# SenseBox-Eye_v1_5.net
KiCad netlist of a schematic drawn in EAGLE
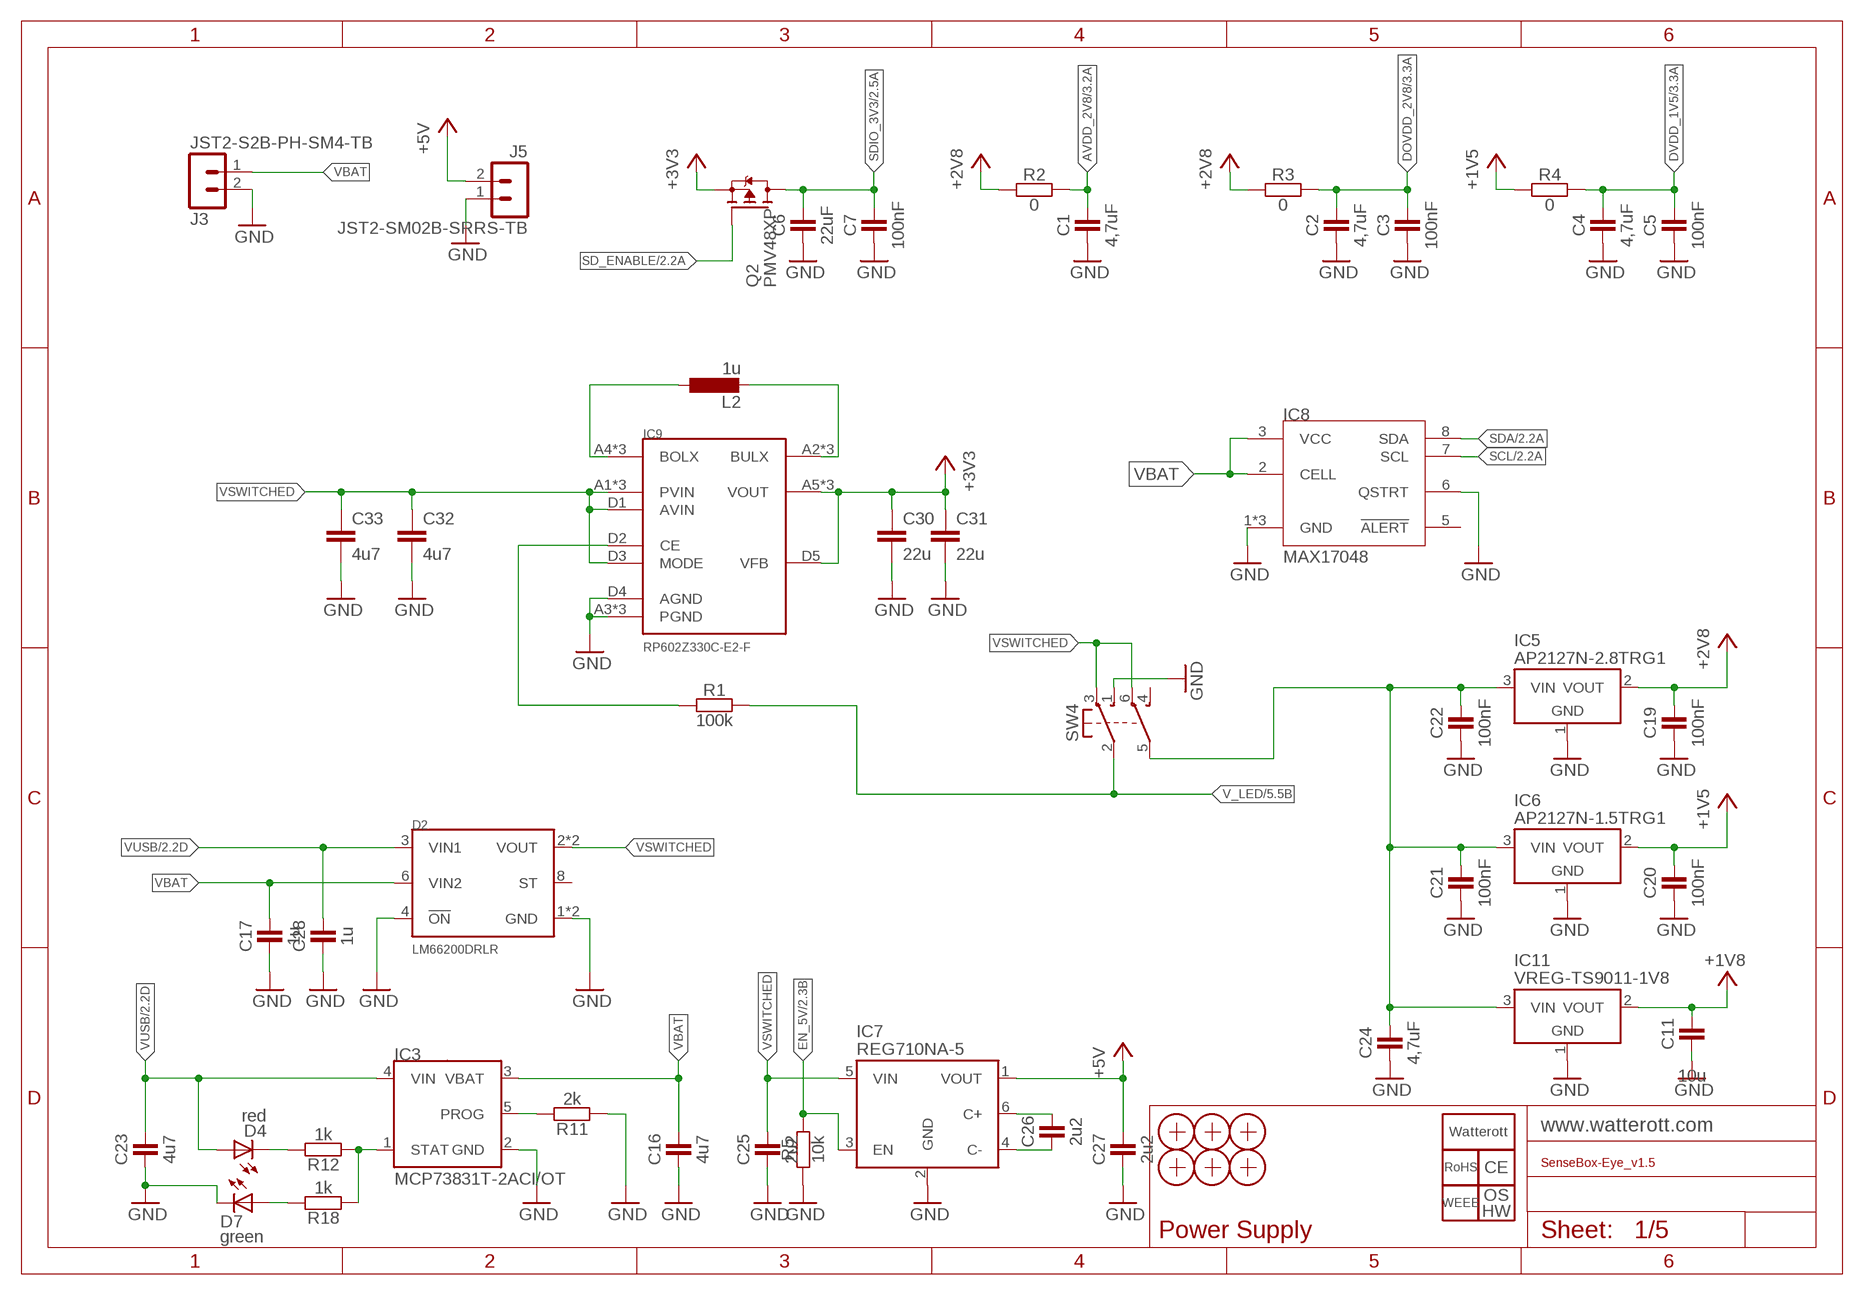
[diagram p0: schematic, sheet 1]
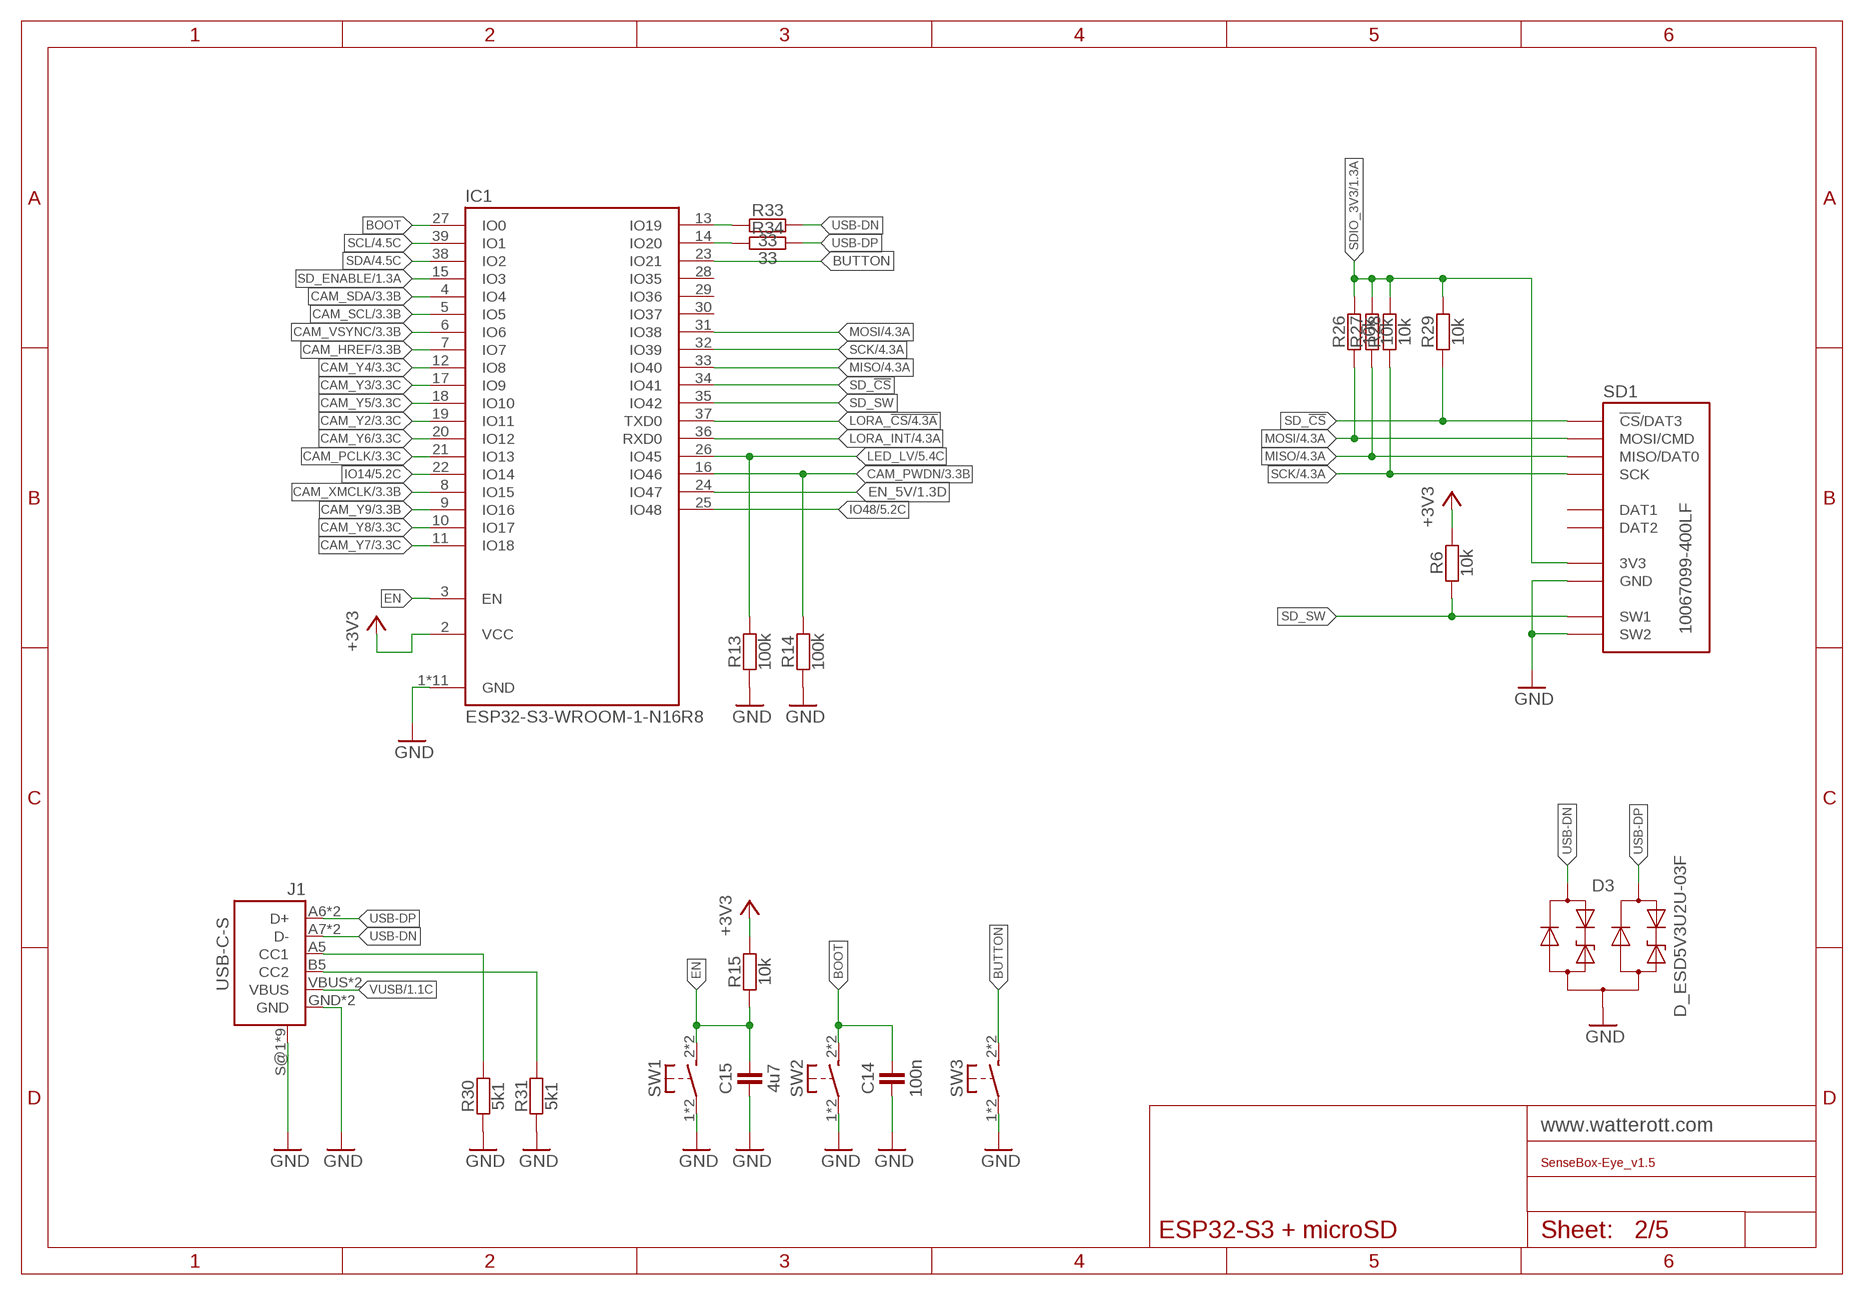
[diagram p1: schematic, sheet 2]
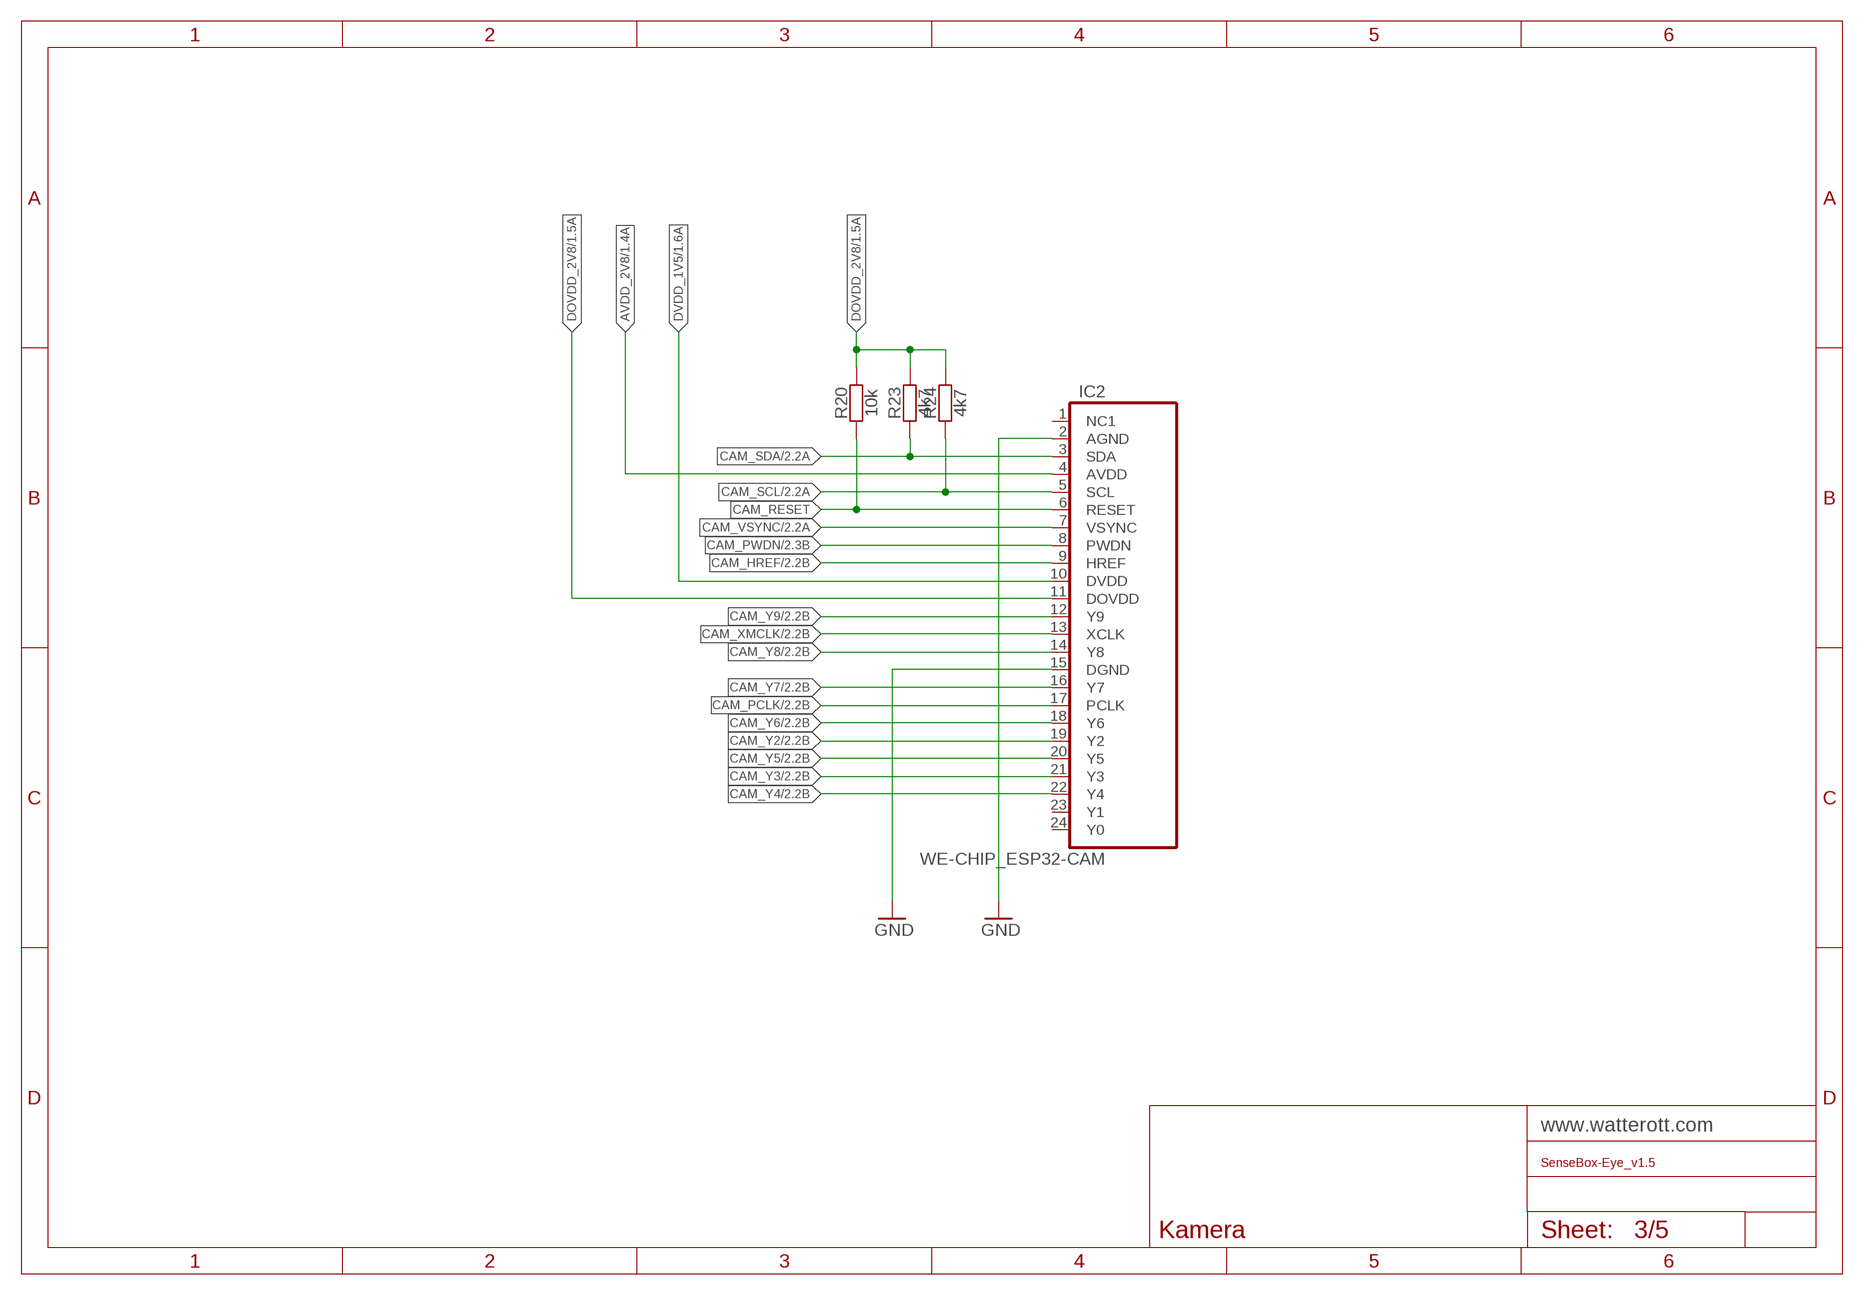
[diagram p2: schematic, sheet 3]
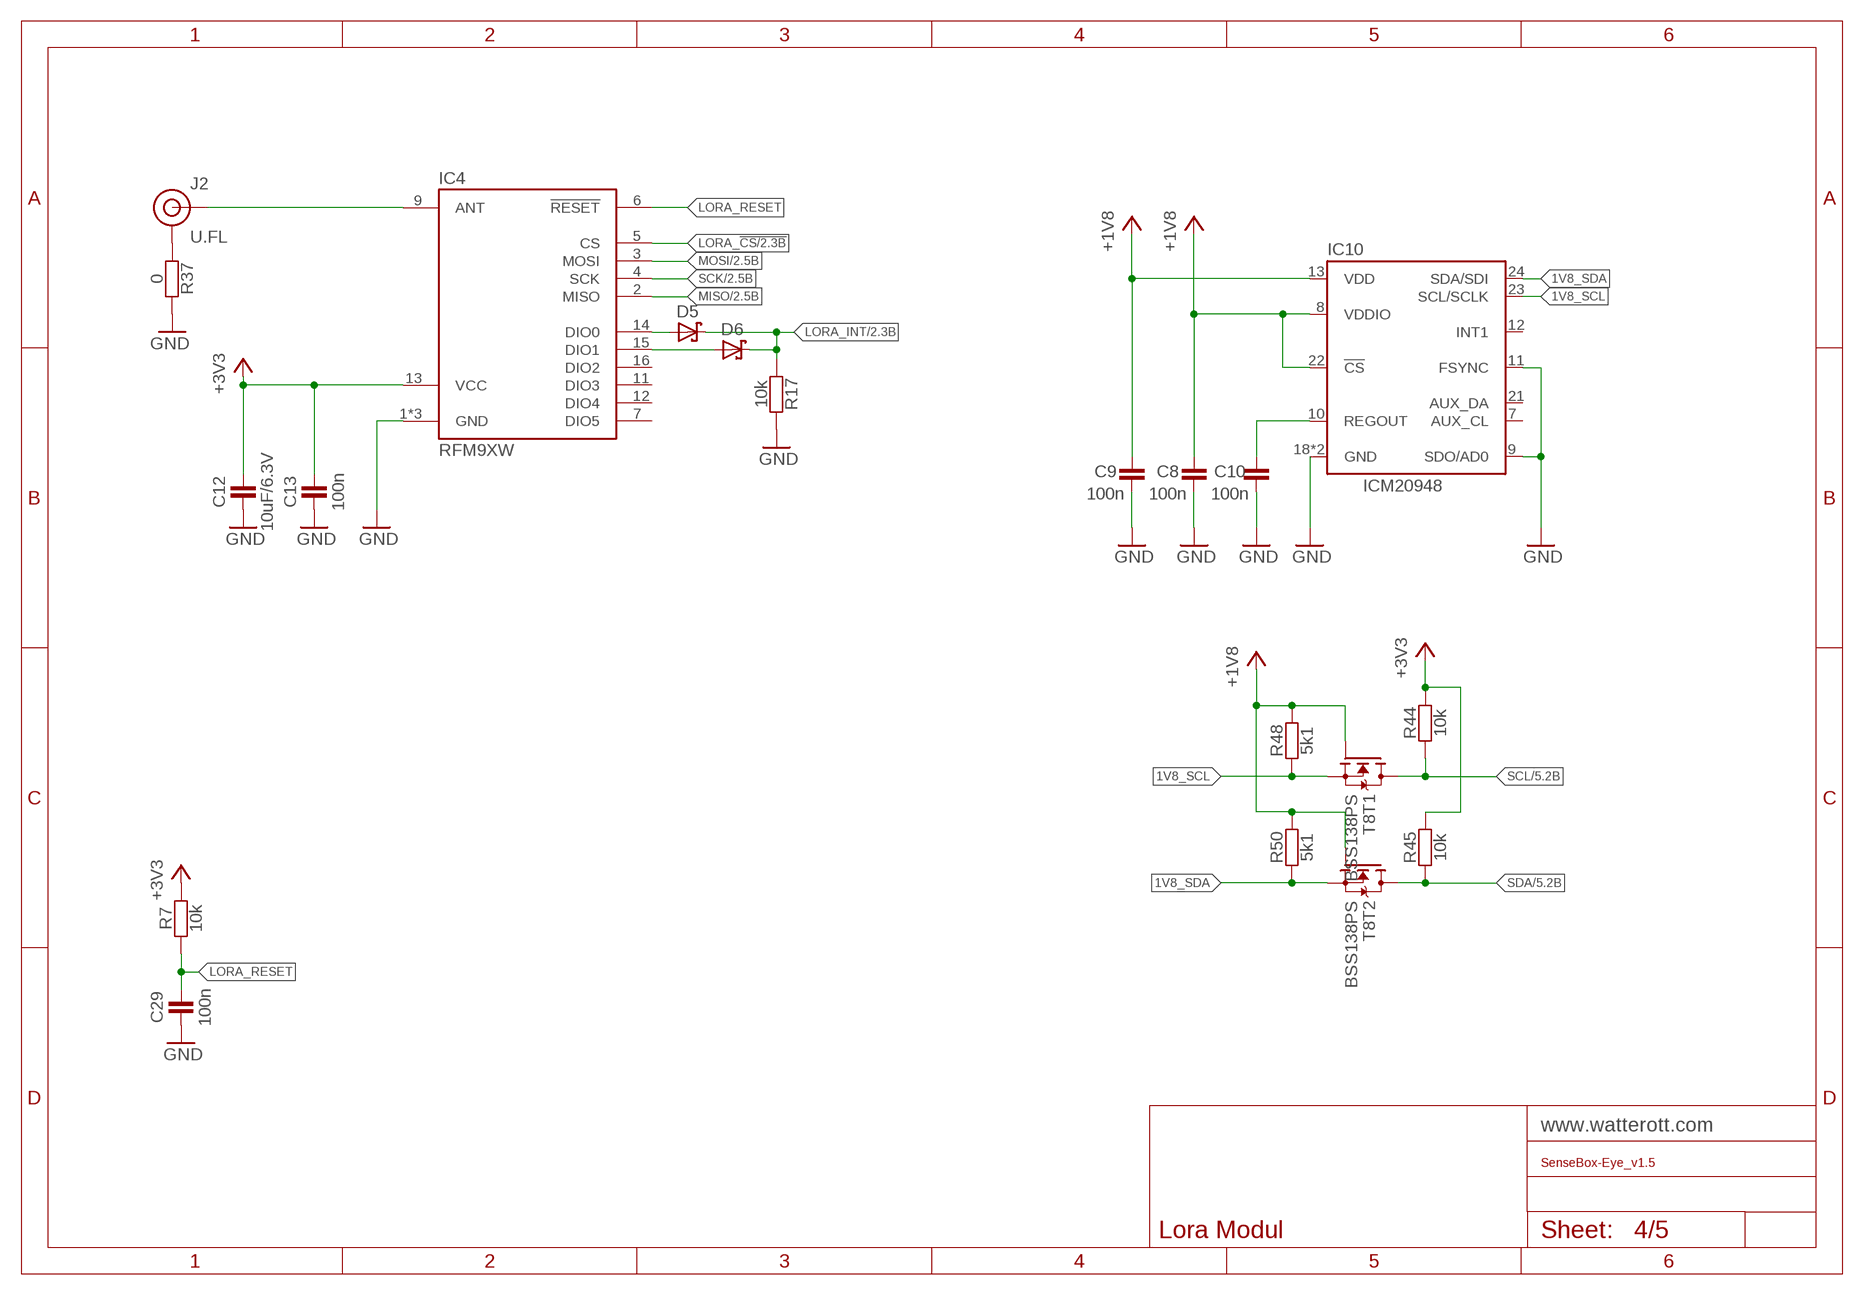
[diagram p3: schematic, sheet 4]
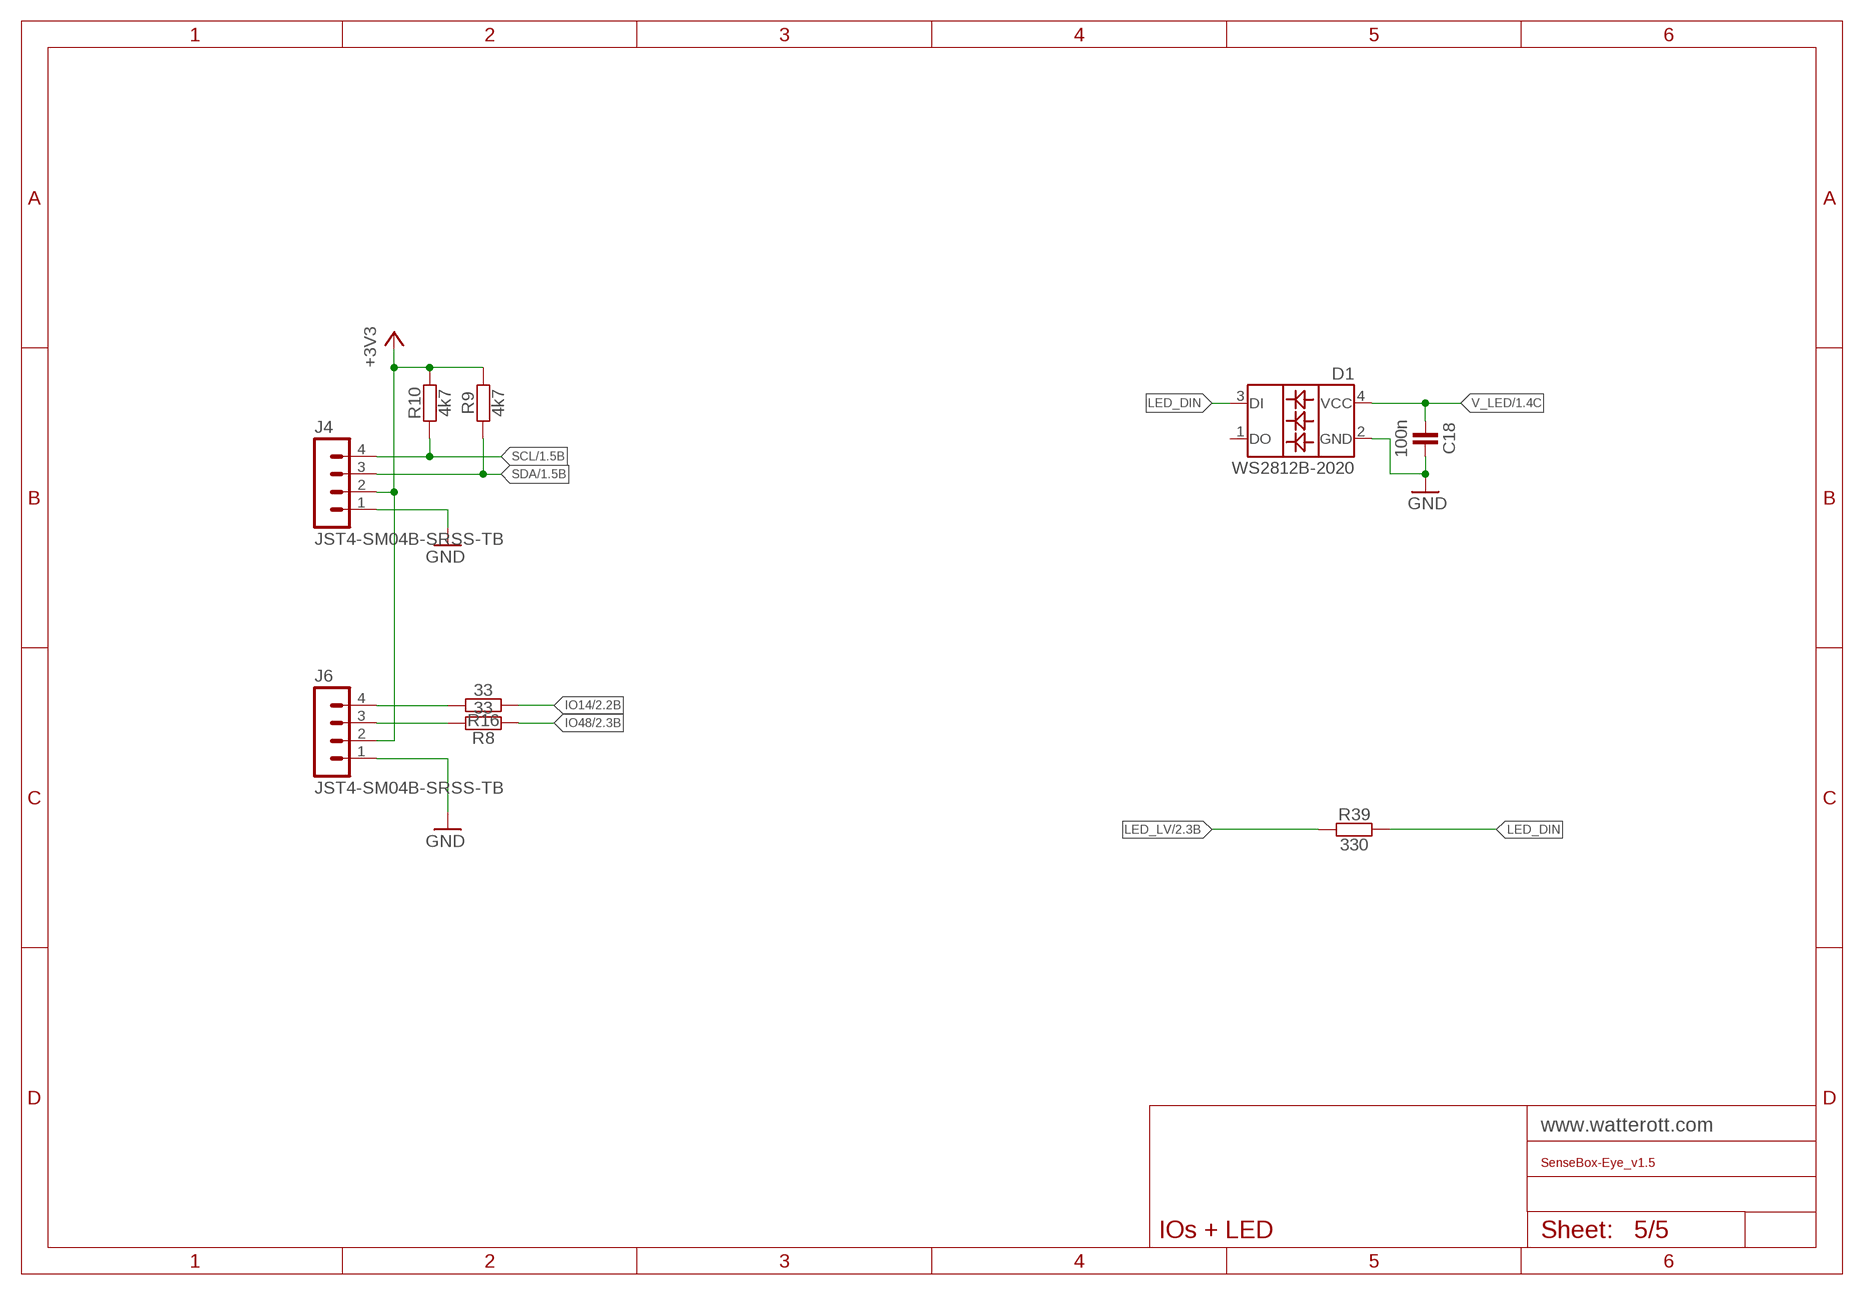
[diagram p4: schematic, sheet 5]

(export (version "E")
  (design (tool "Eeschema 10.0.6"))
  (components
    (comp (ref "C14")
      (value "100n")
      (footprint "eagle-import:C0402")
      (libsource (lib "eagle-import") (part "CAPACITOR-0402"))
    )
    (comp (ref "C15")
      (value "4u7")
      (footprint "eagle-import:C0402")
      (libsource (lib "eagle-import") (part "CAPACITOR-0402"))
    )
    (comp (ref "D3")
      (value "D_ESD5V3U2U-03F")
      (footprint "eagle-import:SOT723")
      (libsource (lib "eagle-import") (part "D_ESD5V3U2U-03F"))
    )
    (comp (ref "IC1")
      (value "ESP32-S3-WROOM-1-N16R8")
      (footprint "eagle-import:ESP32-S3-WROOM-1")
      (libsource (lib "eagle-import") (part "ESP32_S3-WROOM-1"))
    )
    (comp (ref "J1")
      (value "USB-C-S")
      (footprint "eagle-import:USB-C-S")
      (libsource (lib "eagle-import") (part "USB-C-S"))
    )
    (comp (ref "R6")
      (value "10k")
      (footprint "eagle-import:C0402")
      (libsource (lib "eagle-import") (part "RESISTOR-0402"))
    )
    (comp (ref "R13")
      (value "100k")
      (footprint "eagle-import:C0402")
      (libsource (lib "eagle-import") (part "RESISTOR-0402"))
    )
    (comp (ref "R14")
      (value "100k")
      (footprint "eagle-import:C0402")
      (libsource (lib "eagle-import") (part "RESISTOR-0402"))
    )
    (comp (ref "R15")
      (value "10k")
      (footprint "eagle-import:C0402")
      (libsource (lib "eagle-import") (part "RESISTOR-0402"))
    )
    (comp (ref "R26")
      (value "10k")
      (footprint "eagle-import:C0402")
      (libsource (lib "eagle-import") (part "RESISTOR-0402"))
    )
    (comp (ref "R27")
      (value "10k")
      (footprint "eagle-import:C0402")
      (libsource (lib "eagle-import") (part "RESISTOR-0402"))
    )
    (comp (ref "R28")
      (value "10k")
      (footprint "eagle-import:C0402")
      (libsource (lib "eagle-import") (part "RESISTOR-0402"))
    )
    (comp (ref "R29")
      (value "10k")
      (footprint "eagle-import:C0402")
      (libsource (lib "eagle-import") (part "RESISTOR-0402"))
    )
    (comp (ref "R30")
      (value "5k1")
      (footprint "eagle-import:C0402")
      (libsource (lib "eagle-import") (part "RESISTOR-0402"))
    )
    (comp (ref "R31")
      (value "5k1")
      (footprint "eagle-import:C0402")
      (libsource (lib "eagle-import") (part "RESISTOR-0402"))
    )
    (comp (ref "R33")
      (value "33")
      (footprint "eagle-import:C0402")
      (libsource (lib "eagle-import") (part "RESISTOR-0402"))
    )
    (comp (ref "R34")
      (value "33")
      (footprint "eagle-import:C0402")
      (libsource (lib "eagle-import") (part "RESISTOR-0402"))
    )
    (comp (ref "SD1")
      (value "10067099-400LF")
      (footprint "eagle-import:SD_47309XXXX")
      (libsource (lib "eagle-import") (part "SD-CARD-MSD47"))
    )
    (comp (ref "SW1")
      (value "SW-TACTILE-TL3305")
      (footprint "eagle-import:TL3305")
      (libsource (lib "eagle-import") (part "SW-TACTILE-TL3305"))
    )
    (comp (ref "SW2")
      (value "SW-TACTILE-TL3305")
      (footprint "eagle-import:TL3305")
      (libsource (lib "eagle-import") (part "SW-TACTILE-TL3305"))
    )
    (comp (ref "SW3")
      (value "SW-TACTILE-TL3305")
      (footprint "eagle-import:TL3305")
      (libsource (lib "eagle-import") (part "SW-TACTILE-TL3305"))
    )
    (comp (ref "C18")
      (value "100n")
      (footprint "eagle-import:C0402")
      (libsource (lib "eagle-import") (part "CAPACITOR-0402"))
    )
    (comp (ref "D1")
      (value "WS2812B-2020")
      (footprint "eagle-import:WS2812_2020")
      (libsource (lib "eagle-import") (part "WS2812B-2020"))
    )
    (comp (ref "J4")
      (value "JST4-SM04B-SRSS-TB")
      (footprint "eagle-import:JST_SM04B-SRSS-TB")
      (libsource (lib "eagle-import") (part "JST4-SM04B-SRSS-TB"))
    )
    (comp (ref "J6")
      (value "JST4-SM04B-SRSS-TB")
      (footprint "eagle-import:JST_SM04B-SRSS-TB")
      (libsource (lib "eagle-import") (part "JST4-SM04B-SRSS-TB"))
    )
    (comp (ref "R8")
      (value "33")
      (footprint "eagle-import:C0402")
      (libsource (lib "eagle-import") (part "RESISTOR-0402"))
    )
    (comp (ref "R9")
      (value "4k7")
      (footprint "eagle-import:C0402")
      (libsource (lib "eagle-import") (part "RESISTOR-0402"))
    )
    (comp (ref "R10")
      (value "4k7")
      (footprint "eagle-import:C0402")
      (libsource (lib "eagle-import") (part "RESISTOR-0402"))
    )
    (comp (ref "R16")
      (value "33")
      (footprint "eagle-import:C0402")
      (libsource (lib "eagle-import") (part "RESISTOR-0402"))
    )
    (comp (ref "R39")
      (value "330")
      (footprint "eagle-import:C0402")
      (libsource (lib "eagle-import") (part "RESISTOR-0402"))
    )
    (comp (ref "IC2")
      (value "WE-CHIP_ESP32-CAM")
      (footprint "eagle-import:WE-CHIP_FPC24-0.5-CAM")
      (libsource (lib "eagle-import") (part "WE-CHIP_ESP32-CAM"))
    )
    (comp (ref "R20")
      (value "10k")
      (footprint "eagle-import:C0402")
      (libsource (lib "eagle-import") (part "RESISTOR-0402"))
    )
    (comp (ref "R23")
      (value "4k7")
      (footprint "eagle-import:C0402")
      (libsource (lib "eagle-import") (part "RESISTOR-0402"))
    )
    (comp (ref "R24")
      (value "4k7")
      (footprint "eagle-import:C0402")
      (libsource (lib "eagle-import") (part "RESISTOR-0402"))
    )
    (comp (ref "C8")
      (value "100n")
      (footprint "eagle-import:C0402")
      (libsource (lib "eagle-import") (part "CAPACITOR-0402"))
    )
    (comp (ref "C9")
      (value "100n")
      (footprint "eagle-import:C0402")
      (libsource (lib "eagle-import") (part "CAPACITOR-0402"))
    )
    (comp (ref "C10")
      (value "100n")
      (footprint "eagle-import:C0402")
      (libsource (lib "eagle-import") (part "CAPACITOR-0402"))
    )
    (comp (ref "C12")
      (value "10uF/6.3V")
      (footprint "eagle-import:C0402")
      (libsource (lib "eagle-import") (part "CAPACITOR-0402"))
    )
    (comp (ref "C13")
      (value "100n")
      (footprint "eagle-import:C0402")
      (libsource (lib "eagle-import") (part "CAPACITOR-0402"))
    )
    (comp (ref "C29")
      (value "100n")
      (footprint "eagle-import:C0402")
      (libsource (lib "eagle-import") (part "CAPACITOR-0402"))
    )
    (comp (ref "D5")
      (value "D_SCHOTTKY-SOD523")
      (footprint "eagle-import:SOD523")
      (libsource (lib "eagle-import") (part "D_SCHOTTKY-SOD523"))
    )
    (comp (ref "D6")
      (value "D_SCHOTTKY-SOD523")
      (footprint "eagle-import:SOD523")
      (libsource (lib "eagle-import") (part "D_SCHOTTKY-SOD523"))
    )
    (comp (ref "IC4")
      (value "RFM9XW")
      (footprint "eagle-import:RFM9X")
      (libsource (lib "eagle-import") (part "RFM9XW"))
    )
    (comp (ref "IC10")
      (value "ICM20948")
      (footprint "eagle-import:QFN24-3X3")
      (libsource (lib "eagle-import") (part "ICM20948"))
    )
    (comp (ref "J2")
      (value "U.FL")
      (footprint "eagle-import:U.FL")
      (libsource (lib "eagle-import") (part "U.FL"))
    )
    (comp (ref "R7")
      (value "10k")
      (footprint "eagle-import:C0402")
      (libsource (lib "eagle-import") (part "RESISTOR-0402"))
    )
    (comp (ref "R17")
      (value "10k")
      (footprint "eagle-import:C0402")
      (libsource (lib "eagle-import") (part "RESISTOR-0402"))
    )
    (comp (ref "R37")
      (value "0")
      (footprint "eagle-import:C0402")
      (libsource (lib "eagle-import") (part "RESISTOR-0402"))
    )
    (comp (ref "R44")
      (value "10k")
      (footprint "eagle-import:C0402")
      (libsource (lib "eagle-import") (part "RESISTOR-0402"))
    )
    (comp (ref "R45")
      (value "10k")
      (footprint "eagle-import:C0402")
      (libsource (lib "eagle-import") (part "RESISTOR-0402"))
    )
    (comp (ref "R48")
      (value "5k1")
      (footprint "eagle-import:C0402")
      (libsource (lib "eagle-import") (part "RESISTOR-0402"))
    )
    (comp (ref "R50")
      (value "5k1")
      (footprint "eagle-import:C0402")
      (libsource (lib "eagle-import") (part "RESISTOR-0402"))
    )
    (comp (ref "T8")
      (value "BSS138PS")
      (footprint "eagle-import:SOT363")
      (libsource (lib "eagle-import") (part "BSS138PS"))
    )
    (comp (ref "C1")
      (value "4,7uF")
      (footprint "eagle-import:C0402")
      (libsource (lib "eagle-import") (part "CAPACITOR-0402"))
    )
    (comp (ref "C2")
      (value "4,7uF")
      (footprint "eagle-import:C0402")
      (libsource (lib "eagle-import") (part "CAPACITOR-0402"))
    )
    (comp (ref "C3")
      (value "100nF")
      (footprint "eagle-import:C0402")
      (libsource (lib "eagle-import") (part "CAPACITOR-0402"))
    )
    (comp (ref "C4")
      (value "4,7uF")
      (footprint "eagle-import:C0402")
      (libsource (lib "eagle-import") (part "CAPACITOR-0402"))
    )
    (comp (ref "C5")
      (value "100nF")
      (footprint "eagle-import:C0402")
      (libsource (lib "eagle-import") (part "CAPACITOR-0402"))
    )
    (comp (ref "C6")
      (value "22uF")
      (footprint "eagle-import:C0402")
      (libsource (lib "eagle-import") (part "CAPACITOR-0402"))
    )
    (comp (ref "C7")
      (value "100nF")
      (footprint "eagle-import:C0402")
      (libsource (lib "eagle-import") (part "CAPACITOR-0402"))
    )
    (comp (ref "C11")
      (value "10u")
      (footprint "eagle-import:C0402")
      (libsource (lib "eagle-import") (part "CAPACITOR-0402"))
    )
    (comp (ref "C16")
      (value "4u7")
      (footprint "eagle-import:C0402")
      (libsource (lib "eagle-import") (part "CAPACITOR-0402"))
    )
    (comp (ref "C17")
      (value "1u")
      (footprint "eagle-import:C0402")
      (libsource (lib "eagle-import") (part "CAPACITOR-0402"))
    )
    (comp (ref "C19")
      (value "100nF")
      (footprint "eagle-import:C0402")
      (libsource (lib "eagle-import") (part "CAPACITOR-0402"))
    )
    (comp (ref "C20")
      (value "100nF")
      (footprint "eagle-import:C0402")
      (libsource (lib "eagle-import") (part "CAPACITOR-0402"))
    )
    (comp (ref "C21")
      (value "100nF")
      (footprint "eagle-import:C0402")
      (libsource (lib "eagle-import") (part "CAPACITOR-0402"))
    )
    (comp (ref "C22")
      (value "100nF")
      (footprint "eagle-import:C0402")
      (libsource (lib "eagle-import") (part "CAPACITOR-0402"))
    )
    (comp (ref "C23")
      (value "4u7")
      (footprint "eagle-import:C0402")
      (libsource (lib "eagle-import") (part "CAPACITOR-0402"))
    )
    (comp (ref "C24")
      (value "4,7uF")
      (footprint "eagle-import:C0402")
      (libsource (lib "eagle-import") (part "CAPACITOR-0402"))
    )
    (comp (ref "C25")
      (value "2u2")
      (footprint "eagle-import:C0402")
      (libsource (lib "eagle-import") (part "CAPACITOR-0402"))
    )
    (comp (ref "C26")
      (value "2u2")
      (footprint "eagle-import:C0402")
      (libsource (lib "eagle-import") (part "CAPACITOR-0402"))
    )
    (comp (ref "C27")
      (value "2u2")
      (footprint "eagle-import:C0402")
      (libsource (lib "eagle-import") (part "CAPACITOR-0402"))
    )
    (comp (ref "C28")
      (value "1u")
      (footprint "eagle-import:C0402")
      (libsource (lib "eagle-import") (part "CAPACITOR-0402"))
    )
    (comp (ref "C30")
      (value "22u")
      (footprint "eagle-import:0805N")
      (fields (field (name "VOLTAGE") "6V3"))
      (libsource (lib "eagle-import") (part "C_0805N_22U"))
    )
    (comp (ref "C31")
      (value "22u")
      (footprint "eagle-import:0805N")
      (fields (field (name "VOLTAGE") "6V3"))
      (libsource (lib "eagle-import") (part "C_0805N_22U"))
    )
    (comp (ref "C32")
      (value "4u7")
      (footprint "eagle-import:0603N")
      (fields (field (name "VOLTAGE") "6V3"))
      (libsource (lib "eagle-import") (part "C_0603N_4U7"))
    )
    (comp (ref "C33")
      (value "4u7")
      (footprint "eagle-import:0603N")
      (fields (field (name "VOLTAGE") "6V3"))
      (libsource (lib "eagle-import") (part "C_0603N_4U7"))
    )
    (comp (ref "D2")
      (value "LM66200DRLR")
      (footprint "eagle-import:SOT-5X3")
      (libsource (lib "eagle-import") (part "LM66200"))
    )
    (comp (ref "D4")
      (value "red")
      (footprint "eagle-import:0603N")
      (libsource (lib "eagle-import") (part "LED_0603N_RED"))
    )
    (comp (ref "D7")
      (value "green")
      (footprint "eagle-import:0603N")
      (libsource (lib "eagle-import") (part "LED_0603N_RED"))
    )
    (comp (ref "IC3")
      (value "MCP73831T-2ACI/OT")
      (footprint "eagle-import:SOT23-5")
      (libsource (lib "eagle-import") (part "MCP73831_SOT23-5_MCP73831T-2ACI/OT"))
    )
    (comp (ref "IC5")
      (value "AP2127N-2.8TRG1")
      (footprint "eagle-import:SOT23")
      (libsource (lib "eagle-import") (part "VREG-TS9011-3V3"))
    )
    (comp (ref "IC6")
      (value "AP2127N-1.5TRG1")
      (footprint "eagle-import:SOT23")
      (libsource (lib "eagle-import") (part "VREG-TS9011-3V3"))
    )
    (comp (ref "IC7")
      (value "REG710NA-5")
      (footprint "eagle-import:SOT23-6")
      (libsource (lib "eagle-import") (part "REG710NA-5"))
    )
    (comp (ref "IC8")
      (value "MAX17048")
      (footprint "eagle-import:UDFN8_2020")
      (libsource (lib "eagle-import") (part "MAX1704X"))
    )
    (comp (ref "IC9")
      (value "RP602Z330C-E2-F")
      (footprint "eagle-import:WLCSP-20-P1")
      (libsource (lib "eagle-import") (part "RP602_WLCSP-20-P1_RP602Z330C-E2-F"))
    )
    (comp (ref "IC11")
      (value "VREG-TS9011-1V8")
      (footprint "eagle-import:SOT23")
      (libsource (lib "eagle-import") (part "VREG-TS9011-1V8"))
    )
    (comp (ref "J3")
      (value "JST2-S2B-PH-SM4-TB")
      (footprint "eagle-import:JST_S2B-PH-SM4-TB")
      (libsource (lib "eagle-import") (part "JST2-S2B-PH-SM4-TB"))
    )
    (comp (ref "J5")
      (value "JST2-SM02B-SRRS-TB")
      (footprint "eagle-import:JST_SM02B-SRSS-TB")
      (libsource (lib "eagle-import") (part "JST2-SM02B-SRRS-TB"))
    )
    (comp (ref "L2")
      (value "1u")
      (footprint "eagle-import:5040")
      (libsource (lib "eagle-import") (part "L_5040_WE-LQS-1U"))
    )
    (comp (ref "LOGO2")
      (value "LOGO_CE-5")
      (footprint "eagle-import:CE_5MM")
      (libsource (lib "eagle-import") (part "LOGO_CE-5"))
    )
    (comp (ref "LOGO3")
      (value "LOGO_OSHW-2")
      (footprint "eagle-import:OSHW_2MM")
      (libsource (lib "eagle-import") (part "LOGO_OSHW-2"))
    )
    (comp (ref "LOGO4")
      (value "LOGO_ROHS-2")
      (footprint "eagle-import:ROHS_2MM")
      (libsource (lib "eagle-import") (part "LOGO_ROHS-2"))
    )
    (comp (ref "LOGO5")
      (value "LOGO_WEEE-4")
      (footprint "eagle-import:WEEE_4MM")
      (libsource (lib "eagle-import") (part "LOGO_WEEE-4"))
    )
    (comp (ref "LOGO6")
      (value "LOGO_SPARK-2")
      (footprint "eagle-import:SPARK_2MM")
      (libsource (lib "eagle-import") (part "LOGO_SPARK-2"))
    )
    (comp (ref "Q2")
      (value "PMV48XP")
      (footprint "eagle-import:SOT23")
      (fields (field (name "VOLTAGE") "20"))
      (libsource (lib "eagle-import") (part "MOSFET-P_SOT23'_PMV48XP"))
    )
    (comp (ref "R1")
      (value "100k")
      (footprint "eagle-import:C0402")
      (libsource (lib "eagle-import") (part "RESISTOR-0402"))
    )
    (comp (ref "R2")
      (value "0")
      (footprint "eagle-import:C0402")
      (libsource (lib "eagle-import") (part "RESISTOR-0402"))
    )
    (comp (ref "R3")
      (value "0")
      (footprint "eagle-import:C0402")
      (libsource (lib "eagle-import") (part "RESISTOR-0402"))
    )
    (comp (ref "R4")
      (value "0")
      (footprint "eagle-import:C0402")
      (libsource (lib "eagle-import") (part "RESISTOR-0402"))
    )
    (comp (ref "R5")
      (value "10k")
      (footprint "eagle-import:C0402")
      (libsource (lib "eagle-import") (part "RESISTOR-0402"))
    )
    (comp (ref "R11")
      (value "2k")
      (footprint "eagle-import:C0402")
      (libsource (lib "eagle-import") (part "RESISTOR-0402"))
    )
    (comp (ref "R12")
      (value "1k")
      (footprint "eagle-import:C0402")
      (libsource (lib "eagle-import") (part "RESISTOR-0402"))
    )
    (comp (ref "R18")
      (value "1k")
      (footprint "eagle-import:C0402")
      (libsource (lib "eagle-import") (part "RESISTOR-0402"))
    )
    (comp (ref "SW4")
      (value "SW-2UM-CUS22B")
      (footprint "eagle-import:CUS22B")
      (libsource (lib "eagle-import") (part "SW-2UM-CUS22B"))
    )
    (comp (ref "X1")
      (value "PASSER-04")
      (footprint "eagle-import:PASSER_04MM")
      (libsource (lib "eagle-import") (part "PASSER-04"))
    )
    (comp (ref "X2")
      (value "PASSER-04")
      (footprint "eagle-import:PASSER_04MM")
      (libsource (lib "eagle-import") (part "PASSER-04"))
    )
    (comp (ref "X3")
      (value "PASSER-04")
      (footprint "eagle-import:PASSER_04MM")
      (libsource (lib "eagle-import") (part "PASSER-04"))
    )
    (comp (ref "X4")
      (value "PASSER-04")
      (footprint "eagle-import:PASSER_04MM")
      (libsource (lib "eagle-import") (part "PASSER-04"))
    )
    (comp (ref "X5")
      (value "PASSER-04")
      (footprint "eagle-import:PASSER_04MM")
      (libsource (lib "eagle-import") (part "PASSER-04"))
    )
    (comp (ref "X6")
      (value "PASSER-04")
      (footprint "eagle-import:PASSER_04MM")
      (libsource (lib "eagle-import") (part "PASSER-04"))
    )
  )
  (nets
    (net (code "1") (name "+1V5") (class "Default")
      (node (ref "C20") (pin "2") (pinfunction "2_2") (pintype "passive"))
      (node (ref "IC6") (pin "2") (pinfunction "VOUT_2") (pintype "power_in"))
      (node (ref "R4") (pin "1") (pinfunction "1_1") (pintype "passive"))
    )
    (net (code "2") (name "+1V8") (class "Default")
      (node (ref "C11") (pin "2") (pinfunction "2_2") (pintype "passive"))
      (node (ref "C8") (pin "2") (pinfunction "2_2") (pintype "passive"))
      (node (ref "C9") (pin "2") (pinfunction "2_2") (pintype "passive"))
      (node (ref "IC10") (pin "13") (pinfunction "VDD_13") (pintype "power_in"))
      (node (ref "IC10") (pin "22") (pinfunction "~{CS}_22") (pintype "bidirectional"))
      (node (ref "IC10") (pin "8") (pinfunction "VDDIO_8") (pintype "power_in"))
      (node (ref "IC11") (pin "2") (pinfunction "VOUT_2") (pintype "power_in"))
      (node (ref "R48") (pin "2") (pinfunction "2_2") (pintype "passive"))
      (node (ref "R50") (pin "2") (pinfunction "2_2") (pintype "passive"))
      (node (ref "T8") (pin "2") (pinfunction "G_2") (pintype "passive"))
      (node (ref "T8") (pin "5") (pinfunction "G_5") (pintype "passive"))
    )
    (net (code "3") (name "+2V8") (class "Default")
      (node (ref "C19") (pin "2") (pinfunction "2_2") (pintype "passive"))
      (node (ref "IC5") (pin "2") (pinfunction "VOUT_2") (pintype "power_in"))
      (node (ref "R2") (pin "1") (pinfunction "1_1") (pintype "passive"))
      (node (ref "R3") (pin "1") (pinfunction "1_1") (pintype "passive"))
    )
    (net (code "4") (name "+3V3") (class "Default")
      (node (ref "C12") (pin "2") (pinfunction "2_2") (pintype "passive"))
      (node (ref "C13") (pin "2") (pinfunction "2_2") (pintype "passive"))
      (node (ref "C30") (pin "1") (pinfunction "1_1") (pintype "passive"))
      (node (ref "C31") (pin "1") (pinfunction "1_1") (pintype "passive"))
      (node (ref "IC1") (pin "2") (pinfunction "VCC_2") (pintype "power_in"))
      (node (ref "IC4") (pin "13") (pinfunction "VCC_13") (pintype "power_in"))
      (node (ref "IC9") (pin "A5") (pinfunction "VOUT_A5") (pintype "power_in"))
      (node (ref "IC9") (pin "B5") (pinfunction "VOUT_B5") (pintype "power_in"))
      (node (ref "IC9") (pin "C5") (pinfunction "VOUT_C5") (pintype "power_in"))
      (node (ref "IC9") (pin "D5") (pinfunction "VFB_D5") (pintype "input"))
      (node (ref "J4") (pin "2") (pinfunction "2_2") (pintype "passive"))
      (node (ref "J6") (pin "2") (pinfunction "2_2") (pintype "passive"))
      (node (ref "Q2") (pin "2") (pinfunction "S_2") (pintype "passive"))
      (node (ref "R10") (pin "1") (pinfunction "1_1") (pintype "passive"))
      (node (ref "R15") (pin "2") (pinfunction "2_2") (pintype "passive"))
      (node (ref "R44") (pin "2") (pinfunction "2_2") (pintype "passive"))
      (node (ref "R45") (pin "2") (pinfunction "2_2") (pintype "passive"))
      (node (ref "R6") (pin "2") (pinfunction "2_2") (pintype "passive"))
      (node (ref "R7") (pin "2") (pinfunction "2_2") (pintype "passive"))
      (node (ref "R9") (pin "1") (pinfunction "1_1") (pintype "passive"))
    )
    (net (code "5") (name "+5V") (class "Default")
      (node (ref "C27") (pin "2") (pinfunction "2_2") (pintype "passive"))
      (node (ref "IC7") (pin "1") (pinfunction "VOUT_1") (pintype "power_in"))
      (node (ref "J5") (pin "2") (pinfunction "2_2") (pintype "passive"))
    )
    (net (code "6") (name "1V8_SCL") (class "Default")
      (node (ref "IC10") (pin "23") (pinfunction "SCL/SCLK_23") (pintype "bidirectional"))
      (node (ref "R48") (pin "1") (pinfunction "1_1") (pintype "passive"))
      (node (ref "T8") (pin "1") (pinfunction "S_1") (pintype "passive"))
    )
    (net (code "7") (name "1V8_SDA") (class "Default")
      (node (ref "IC10") (pin "24") (pinfunction "SDA/SDI_24") (pintype "bidirectional"))
      (node (ref "R50") (pin "1") (pinfunction "1_1") (pintype "passive"))
      (node (ref "T8") (pin "4") (pinfunction "S_4") (pintype "passive"))
    )
    (net (code "8") (name "AVDD_2V8") (class "Default")
      (node (ref "C1") (pin "2") (pinfunction "2_2") (pintype "passive"))
      (node (ref "IC2") (pin "4") (pinfunction "AVDD_4") (pintype "bidirectional"))
      (node (ref "R2") (pin "2") (pinfunction "2_2") (pintype "passive"))
    )
    (net (code "9") (name "BOOT") (class "Default")
      (node (ref "C14") (pin "2") (pinfunction "2_2") (pintype "passive"))
      (node (ref "IC1") (pin "27") (pinfunction "IO0_27") (pintype "bidirectional"))
      (node (ref "SW2") (pin "2") (pinfunction "S1_2") (pintype "passive"))
      (node (ref "SW2") (pin "3") (pinfunction "S1_3") (pintype "passive"))
    )
    (net (code "10") (name "BUTTON") (class "Default")
      (node (ref "IC1") (pin "23") (pinfunction "IO21_23") (pintype "bidirectional"))
      (node (ref "SW3") (pin "2") (pinfunction "S1_2") (pintype "passive"))
      (node (ref "SW3") (pin "3") (pinfunction "S1_3") (pintype "passive"))
    )
    (net (code "11") (name "CAM_HREF") (class "Default")
      (node (ref "IC1") (pin "7") (pinfunction "IO7_7") (pintype "bidirectional"))
      (node (ref "IC2") (pin "9") (pinfunction "HREF_9") (pintype "bidirectional"))
    )
    (net (code "12") (name "CAM_PCLK") (class "Default")
      (node (ref "IC1") (pin "21") (pinfunction "IO13_21") (pintype "bidirectional"))
      (node (ref "IC2") (pin "17") (pinfunction "PCLK_17") (pintype "bidirectional"))
    )
    (net (code "13") (name "CAM_PWDN") (class "Default")
      (node (ref "IC1") (pin "16") (pinfunction "IO46_16") (pintype "bidirectional"))
      (node (ref "IC2") (pin "8") (pinfunction "PWDN_8") (pintype "bidirectional"))
      (node (ref "R14") (pin "2") (pinfunction "2_2") (pintype "passive"))
    )
    (net (code "14") (name "CAM_RESET") (class "Default")
      (node (ref "IC2") (pin "6") (pinfunction "RESET_6") (pintype "bidirectional"))
      (node (ref "R20") (pin "1") (pinfunction "1_1") (pintype "passive"))
    )
    (net (code "15") (name "CAM_SCL") (class "Default")
      (node (ref "IC1") (pin "5") (pinfunction "IO5_5") (pintype "bidirectional"))
      (node (ref "IC2") (pin "5") (pinfunction "SCL_5") (pintype "bidirectional"))
      (node (ref "R24") (pin "1") (pinfunction "1_1") (pintype "passive"))
    )
    (net (code "16") (name "CAM_SDA") (class "Default")
      (node (ref "IC1") (pin "4") (pinfunction "IO4_4") (pintype "bidirectional"))
      (node (ref "IC2") (pin "3") (pinfunction "SDA_3") (pintype "bidirectional"))
      (node (ref "R23") (pin "1") (pinfunction "1_1") (pintype "passive"))
    )
    (net (code "17") (name "CAM_VSYNC") (class "Default")
      (node (ref "IC1") (pin "6") (pinfunction "IO6_6") (pintype "bidirectional"))
      (node (ref "IC2") (pin "7") (pinfunction "VSYNC_7") (pintype "bidirectional"))
    )
    (net (code "18") (name "CAM_XMCLK") (class "Default")
      (node (ref "IC1") (pin "8") (pinfunction "IO15_8") (pintype "bidirectional"))
      (node (ref "IC2") (pin "13") (pinfunction "XCLK_13") (pintype "bidirectional"))
    )
    (net (code "19") (name "CAM_Y2") (class "Default")
      (node (ref "IC1") (pin "19") (pinfunction "IO11_19") (pintype "bidirectional"))
      (node (ref "IC2") (pin "19") (pinfunction "Y2_19") (pintype "bidirectional"))
    )
    (net (code "20") (name "CAM_Y3") (class "Default")
      (node (ref "IC1") (pin "17") (pinfunction "IO9_17") (pintype "bidirectional"))
      (node (ref "IC2") (pin "21") (pinfunction "Y3_21") (pintype "bidirectional"))
    )
    (net (code "21") (name "CAM_Y4") (class "Default")
      (node (ref "IC1") (pin "12") (pinfunction "IO8_12") (pintype "bidirectional"))
      (node (ref "IC2") (pin "22") (pinfunction "Y4_22") (pintype "bidirectional"))
    )
    (net (code "22") (name "CAM_Y5") (class "Default")
      (node (ref "IC1") (pin "18") (pinfunction "IO10_18") (pintype "bidirectional"))
      (node (ref "IC2") (pin "20") (pinfunction "Y5_20") (pintype "bidirectional"))
    )
    (net (code "23") (name "CAM_Y6") (class "Default")
      (node (ref "IC1") (pin "20") (pinfunction "IO12_20") (pintype "bidirectional"))
      (node (ref "IC2") (pin "18") (pinfunction "Y6_18") (pintype "bidirectional"))
    )
    (net (code "24") (name "CAM_Y7") (class "Default")
      (node (ref "IC1") (pin "11") (pinfunction "IO18_11") (pintype "bidirectional"))
      (node (ref "IC2") (pin "16") (pinfunction "Y7_16") (pintype "bidirectional"))
    )
    (net (code "25") (name "CAM_Y8") (class "Default")
      (node (ref "IC1") (pin "10") (pinfunction "IO17_10") (pintype "bidirectional"))
      (node (ref "IC2") (pin "14") (pinfunction "Y8_14") (pintype "bidirectional"))
    )
    (net (code "26") (name "CAM_Y9") (class "Default")
      (node (ref "IC1") (pin "9") (pinfunction "IO16_9") (pintype "bidirectional"))
      (node (ref "IC2") (pin "12") (pinfunction "Y9_12") (pintype "bidirectional"))
    )
    (net (code "27") (name "DOVDD_2V8") (class "Default")
      (node (ref "C2") (pin "2") (pinfunction "2_2") (pintype "passive"))
      (node (ref "C3") (pin "2") (pinfunction "2_2") (pintype "passive"))
      (node (ref "IC2") (pin "11") (pinfunction "DOVDD_11") (pintype "bidirectional"))
      (node (ref "R20") (pin "2") (pinfunction "2_2") (pintype "passive"))
      (node (ref "R23") (pin "2") (pinfunction "2_2") (pintype "passive"))
      (node (ref "R24") (pin "2") (pinfunction "2_2") (pintype "passive"))
      (node (ref "R3") (pin "2") (pinfunction "2_2") (pintype "passive"))
    )
    (net (code "28") (name "DVDD_1V5") (class "Default")
      (node (ref "C4") (pin "2") (pinfunction "2_2") (pintype "passive"))
      (node (ref "C5") (pin "2") (pinfunction "2_2") (pintype "passive"))
      (node (ref "IC2") (pin "10") (pinfunction "DVDD_10") (pintype "bidirectional"))
      (node (ref "R4") (pin "2") (pinfunction "2_2") (pintype "passive"))
    )
    (net (code "29") (name "EN") (class "Default")
      (node (ref "C15") (pin "2") (pinfunction "2_2") (pintype "passive"))
      (node (ref "IC1") (pin "3") (pinfunction "EN_3") (pintype "bidirectional"))
      (node (ref "R15") (pin "1") (pinfunction "1_1") (pintype "passive"))
      (node (ref "SW1") (pin "2") (pinfunction "S1_2") (pintype "passive"))
      (node (ref "SW1") (pin "3") (pinfunction "S1_3") (pintype "passive"))
    )
    (net (code "30") (name "EN_5V") (class "Default")
      (node (ref "IC1") (pin "24") (pinfunction "IO47_24") (pintype "bidirectional"))
      (node (ref "IC7") (pin "3") (pinfunction "EN_3") (pintype "passive"))
      (node (ref "R5") (pin "2") (pinfunction "2_2") (pintype "passive"))
    )
    (net (code "31") (name "GND") (class "Default")
      (node (ref "C1") (pin "1") (pinfunction "1_1") (pintype "passive"))
      (node (ref "C10") (pin "1") (pinfunction "1_1") (pintype "passive"))
      (node (ref "C11") (pin "1") (pinfunction "1_1") (pintype "passive"))
      (node (ref "C12") (pin "1") (pinfunction "1_1") (pintype "passive"))
      (node (ref "C13") (pin "1") (pinfunction "1_1") (pintype "passive"))
      (node (ref "C14") (pin "1") (pinfunction "1_1") (pintype "passive"))
      (node (ref "C15") (pin "1") (pinfunction "1_1") (pintype "passive"))
      (node (ref "C16") (pin "1") (pinfunction "1_1") (pintype "passive"))
      (node (ref "C17") (pin "1") (pinfunction "1_1") (pintype "passive"))
      (node (ref "C18") (pin "1") (pinfunction "1_1") (pintype "passive"))
      (node (ref "C19") (pin "1") (pinfunction "1_1") (pintype "passive"))
      (node (ref "C2") (pin "1") (pinfunction "1_1") (pintype "passive"))
      (node (ref "C20") (pin "1") (pinfunction "1_1") (pintype "passive"))
      (node (ref "C21") (pin "1") (pinfunction "1_1") (pintype "passive"))
      (node (ref "C22") (pin "1") (pinfunction "1_1") (pintype "passive"))
      (node (ref "C23") (pin "1") (pinfunction "1_1") (pintype "passive"))
      (node (ref "C24") (pin "1") (pinfunction "1_1") (pintype "passive"))
      (node (ref "C25") (pin "1") (pinfunction "1_1") (pintype "passive"))
      (node (ref "C27") (pin "1") (pinfunction "1_1") (pintype "passive"))
      (node (ref "C28") (pin "1") (pinfunction "1_1") (pintype "passive"))
      (node (ref "C29") (pin "1") (pinfunction "1_1") (pintype "passive"))
      (node (ref "C3") (pin "1") (pinfunction "1_1") (pintype "passive"))
      (node (ref "C30") (pin "2") (pinfunction "2_2") (pintype "passive"))
      (node (ref "C31") (pin "2") (pinfunction "2_2") (pintype "passive"))
      (node (ref "C32") (pin "2") (pinfunction "2_2") (pintype "passive"))
      (node (ref "C33") (pin "2") (pinfunction "2_2") (pintype "passive"))
      (node (ref "C4") (pin "1") (pinfunction "1_1") (pintype "passive"))
      (node (ref "C5") (pin "1") (pinfunction "1_1") (pintype "passive"))
      (node (ref "C6") (pin "1") (pinfunction "1_1") (pintype "passive"))
      (node (ref "C7") (pin "1") (pinfunction "1_1") (pintype "passive"))
      (node (ref "C8") (pin "1") (pinfunction "1_1") (pintype "passive"))
      (node (ref "C9") (pin "1") (pinfunction "1_1") (pintype "passive"))
      (node (ref "D1") (pin "2") (pinfunction "GND_2") (pintype "power_in"))
      (node (ref "D2") (pin "1") (pinfunction "GND_1") (pintype "power_in"))
      (node (ref "D2") (pin "4") (pinfunction "~{ON}_4") (pintype "input"))
      (node (ref "D2") (pin "5") (pinfunction "GND_5") (pintype "power_in"))
      (node (ref "D3") (pin "3") (pinfunction "A_3") (pintype "passive"))
      (node (ref "D7") (pin "C") (pinfunction "C_C") (pintype "passive"))
      (node (ref "IC1") (pin "1") (pinfunction "GND_1") (pintype "power_in"))
      (node (ref "IC1") (pin "40") (pinfunction "GND_40") (pintype "power_in"))
      (node (ref "IC1") (pin "P$1") (pinfunction "GND_P$1") (pintype "power_in"))
      (node (ref "IC1") (pin "P$2") (pinfunction "GND_P$2") (pintype "power_in"))
      (node (ref "IC1") (pin "P$3") (pinfunction "GND_P$3") (pintype "power_in"))
      (node (ref "IC1") (pin "P$4") (pinfunction "GND_P$4") (pintype "power_in"))
      (node (ref "IC1") (pin "P$5") (pinfunction "GND_P$5") (pintype "power_in"))
      (node (ref "IC1") (pin "P$6") (pinfunction "GND_P$6") (pintype "power_in"))
      (node (ref "IC1") (pin "P$7") (pinfunction "GND_P$7") (pintype "power_in"))
      (node (ref "IC1") (pin "P$8") (pinfunction "GND_P$8") (pintype "power_in"))
      (node (ref "IC1") (pin "P$9") (pinfunction "GND_P$9") (pintype "power_in"))
      (node (ref "IC10") (pin "11") (pinfunction "FSYNC_11") (pintype "input"))
      (node (ref "IC10") (pin "18") (pinfunction "GND_18") (pintype "power_in"))
      (node (ref "IC10") (pin "20") (pinfunction "GND_20") (pintype "power_in"))
      (node (ref "IC10") (pin "9") (pinfunction "SDO/AD0_9") (pintype "input"))
      (node (ref "IC11") (pin "1") (pinfunction "GND_1") (pintype "power_in"))
      (node (ref "IC2") (pin "15") (pinfunction "DGND_15") (pintype "bidirectional"))
      (node (ref "IC2") (pin "2") (pinfunction "AGND_2") (pintype "bidirectional"))
      (node (ref "IC3") (pin "2") (pinfunction "GND_2") (pintype "power_in"))
      (node (ref "IC4") (pin "1") (pinfunction "GND_1") (pintype "power_in"))
      (node (ref "IC4") (pin "10") (pinfunction "GND_10") (pintype "power_in"))
      (node (ref "IC4") (pin "8") (pinfunction "GND_8") (pintype "power_in"))
      (node (ref "IC5") (pin "1") (pinfunction "GND_1") (pintype "power_in"))
      (node (ref "IC6") (pin "1") (pinfunction "GND_1") (pintype "power_in"))
      (node (ref "IC7") (pin "2") (pinfunction "GND_2") (pintype "power_in"))
      (node (ref "IC8") (pin "1") (pinfunction "GND_1") (pintype "bidirectional"))
      (node (ref "IC8") (pin "4") (pinfunction "GND_4") (pintype "bidirectional"))
      (node (ref "IC8") (pin "6") (pinfunction "QSTRT_6") (pintype "bidirectional"))
      (node (ref "IC8") (pin "TP") (pinfunction "GND_TP") (pintype "bidirectional"))
      (node (ref "IC9") (pin "A3") (pinfunction "PGND_A3") (pintype "power_in"))
      (node (ref "IC9") (pin "B3") (pinfunction "PGND_B3") (pintype "power_in"))
      (node (ref "IC9") (pin "C3") (pinfunction "PGND_C3") (pintype "power_in"))
      (node (ref "IC9") (pin "D4") (pinfunction "AGND_D4") (pintype "power_in"))
      (node (ref "J1") (pin "GND") (pinfunction "GND_GND") (pintype "power_in"))
      (node (ref "J1") (pin "GND2") (pinfunction "GND_GND2") (pintype "power_in"))
      (node (ref "J1") (pin "S@1") (pinfunction "SHIELD_S@1") (pintype "passive"))
      (node (ref "J1") (pin "S@2") (pinfunction "SHIELD_S@2") (pintype "passive"))
      (node (ref "J1") (pin "S@3") (pinfunction "SHIELD_S@3") (pintype "passive"))
      (node (ref "J1") (pin "S@4") (pinfunction "SHIELD_S@4") (pintype "passive"))
      (node (ref "J1") (pin "S@5") (pinfunction "SHIELD_S@5") (pintype "passive"))
      (node (ref "J1") (pin "S@6") (pinfunction "SHIELD_S@6") (pintype "passive"))
      (node (ref "J1") (pin "S@7") (pinfunction "SHIELD_S@7") (pintype "passive"))
      (node (ref "J1") (pin "S@8") (pinfunction "SHIELD_S@8") (pintype "passive"))
      (node (ref "J1") (pin "S@9") (pinfunction "SHIELD_S@9") (pintype "passive"))
      (node (ref "J3") (pin "2") (pinfunction "2_2") (pintype "passive"))
      (node (ref "J4") (pin "1") (pinfunction "1_1") (pintype "passive"))
      (node (ref "J5") (pin "1") (pinfunction "1_1") (pintype "passive"))
      (node (ref "J6") (pin "1") (pinfunction "1_1") (pintype "passive"))
      (node (ref "R11") (pin "1") (pinfunction "1_1") (pintype "passive"))
      (node (ref "R13") (pin "1") (pinfunction "1_1") (pintype "passive"))
      (node (ref "R14") (pin "1") (pinfunction "1_1") (pintype "passive"))
      (node (ref "R17") (pin "1") (pinfunction "1_1") (pintype "passive"))
      (node (ref "R30") (pin "1") (pinfunction "1_1") (pintype "passive"))
      (node (ref "R31") (pin "1") (pinfunction "1_1") (pintype "passive"))
      (node (ref "R37") (pin "1") (pinfunction "1_1") (pintype "passive"))
      (node (ref "R5") (pin "1") (pinfunction "1_1") (pintype "passive"))
      (node (ref "SD1") (pin "GND") (pinfunction "GND_GND") (pintype "bidirectional"))
      (node (ref "SD1") (pin "GND@1") (pinfunction "GND_GND@1") (pintype "bidirectional"))
      (node (ref "SD1") (pin "GND@2") (pinfunction "GND_GND@2") (pintype "bidirectional"))
      (node (ref "SD1") (pin "SW2") (pinfunction "SW2_SW2") (pintype "bidirectional"))
      (node (ref "SW1") (pin "1") (pinfunction "P1_1") (pintype "passive"))
      (node (ref "SW1") (pin "4") (pinfunction "P1_4") (pintype "passive"))
      (node (ref "SW2") (pin "1") (pinfunction "P1_1") (pintype "passive"))
      (node (ref "SW2") (pin "4") (pinfunction "P1_4") (pintype "passive"))
      (node (ref "SW3") (pin "1") (pinfunction "P1_1") (pintype "passive"))
      (node (ref "SW3") (pin "4") (pinfunction "P1_4") (pintype "passive"))
      (node (ref "SW4") (pin "1") (pinfunction "NO1_1") (pintype "passive"))
    )
    (net (code "32") (name "IO14") (class "Default")
      (node (ref "IC1") (pin "22") (pinfunction "IO14_22") (pintype "bidirectional"))
      (node (ref "R16") (pin "2") (pinfunction "2_2") (pintype "passive"))
    )
    (net (code "33") (name "IO48") (class "Default")
      (node (ref "IC1") (pin "25") (pinfunction "IO48_25") (pintype "bidirectional"))
      (node (ref "R8") (pin "2") (pinfunction "2_2") (pintype "passive"))
    )
    (net (code "34") (name "LED_DIN") (class "Default")
      (node (ref "D1") (pin "3") (pinfunction "DI_3") (pintype "bidirectional"))
      (node (ref "R39") (pin "2") (pinfunction "2_2") (pintype "passive"))
    )
    (net (code "35") (name "LED_LV") (class "Default")
      (node (ref "IC1") (pin "26") (pinfunction "IO45_26") (pintype "bidirectional"))
      (node (ref "R13") (pin "2") (pinfunction "2_2") (pintype "passive"))
      (node (ref "R39") (pin "1") (pinfunction "1_1") (pintype "passive"))
    )
    (net (code "36") (name "LORA_INT") (class "Default")
      (node (ref "D5") (pin "C") (pinfunction "C_C") (pintype "passive"))
      (node (ref "D6") (pin "C") (pinfunction "C_C") (pintype "passive"))
      (node (ref "IC1") (pin "36") (pinfunction "RXD0_36") (pintype "bidirectional"))
      (node (ref "R17") (pin "2") (pinfunction "2_2") (pintype "passive"))
    )
    (net (code "37") (name "LORA_RESET") (class "Default")
      (node (ref "C29") (pin "2") (pinfunction "2_2") (pintype "passive"))
      (node (ref "IC4") (pin "6") (pinfunction "~{RESET}_6") (pintype "input"))
      (node (ref "R7") (pin "1") (pinfunction "1_1") (pintype "passive"))
    )
    (net (code "38") (name "LORA_~{CS}") (class "Default")
      (node (ref "IC1") (pin "37") (pinfunction "TXD0_37") (pintype "bidirectional"))
      (node (ref "IC4") (pin "5") (pinfunction "CS_5") (pintype "input"))
    )
    (net (code "39") (name "MISO") (class "Default")
      (node (ref "IC1") (pin "33") (pinfunction "IO40_33") (pintype "bidirectional"))
      (node (ref "IC4") (pin "2") (pinfunction "MISO_2") (pintype "output"))
      (node (ref "R27") (pin "1") (pinfunction "1_1") (pintype "passive"))
      (node (ref "SD1") (pin "MISO") (pinfunction "MISO/DAT0_MISO") (pintype "bidirectional"))
    )
    (net (code "40") (name "MOSI") (class "Default")
      (node (ref "IC1") (pin "31") (pinfunction "IO38_31") (pintype "bidirectional"))
      (node (ref "IC4") (pin "3") (pinfunction "MOSI_3") (pintype "input"))
      (node (ref "R26") (pin "1") (pinfunction "1_1") (pintype "passive"))
      (node (ref "SD1") (pin "MOSI") (pinfunction "MOSI/CMD_MOSI") (pintype "bidirectional"))
    )
    (net (code "41") (name "Net-(D4-PadC)") (class "Default")
      (node (ref "D4") (pin "C") (pinfunction "C_C") (pintype "passive"))
      (node (ref "R12") (pin "2") (pinfunction "2_2") (pintype "passive"))
    )
    (net (code "42") (name "Net-(D7-PadA)") (class "Default")
      (node (ref "D7") (pin "A") (pinfunction "A_A") (pintype "passive"))
      (node (ref "R18") (pin "2") (pinfunction "2_2") (pintype "passive"))
    )
    (net (code "43") (name "Net-(IC1-IO19)") (class "Default")
      (node (ref "IC1") (pin "13") (pinfunction "IO19_13") (pintype "bidirectional"))
      (node (ref "R33") (pin "1") (pinfunction "1_1") (pintype "passive"))
    )
    (net (code "44") (name "Net-(IC1-IO20)") (class "Default")
      (node (ref "IC1") (pin "14") (pinfunction "IO20_14") (pintype "bidirectional"))
      (node (ref "R34") (pin "1") (pinfunction "1_1") (pintype "passive"))
    )
    (net (code "45") (name "Net-(IC3-PROG)") (class "Default")
      (node (ref "IC3") (pin "5") (pinfunction "PROG_5") (pintype "input"))
      (node (ref "R11") (pin "2") (pinfunction "2_2") (pintype "passive"))
    )
    (net (code "46") (name "Net-(IC3-STAT)") (class "Default")
      (node (ref "IC3") (pin "1") (pinfunction "STAT_1") (pintype "open_collector"))
      (node (ref "R12") (pin "1") (pinfunction "1_1") (pintype "passive"))
      (node (ref "R18") (pin "1") (pinfunction "1_1") (pintype "passive"))
    )
    (net (code "47") (name "Net-(IC4-ANT)") (class "Default")
      (node (ref "IC4") (pin "9") (pinfunction "ANT_9") (pintype "bidirectional"))
      (node (ref "J2") (pin "FEED") (pinfunction "SIGNAL_FEED") (pintype "bidirectional"))
    )
    (net (code "48") (name "Net-(IC4-DIO0)") (class "Default")
      (node (ref "D5") (pin "A") (pinfunction "A_A") (pintype "passive"))
      (node (ref "IC4") (pin "14") (pinfunction "DIO0_14") (pintype "bidirectional"))
    )
    (net (code "49") (name "Net-(IC4-DIO1)") (class "Default")
      (node (ref "D6") (pin "A") (pinfunction "A_A") (pintype "passive"))
      (node (ref "IC4") (pin "15") (pinfunction "DIO1_15") (pintype "bidirectional"))
    )
    (net (code "50") (name "Net-(IC7-C+)") (class "Default")
      (node (ref "C26") (pin "2") (pinfunction "2_2") (pintype "passive"))
      (node (ref "IC7") (pin "6") (pinfunction "C+_6") (pintype "passive"))
    )
    (net (code "51") (name "Net-(IC7-C-)") (class "Default")
      (node (ref "C26") (pin "1") (pinfunction "1_1") (pintype "passive"))
      (node (ref "IC7") (pin "4") (pinfunction "C-_4") (pintype "passive"))
    )
    (net (code "52") (name "Net-(IC9-BOLX-PadA4)") (class "Default")
      (node (ref "IC9") (pin "A4") (pinfunction "BOLX_A4") (pintype "output"))
      (node (ref "IC9") (pin "B4") (pinfunction "BOLX_B4") (pintype "output"))
      (node (ref "IC9") (pin "C4") (pinfunction "BOLX_C4") (pintype "output"))
      (node (ref "L2") (pin "1") (pinfunction "1_1") (pintype "passive"))
    )
    (net (code "53") (name "Net-(IC9-BULX-PadA2)") (class "Default")
      (node (ref "IC9") (pin "A2") (pinfunction "BULX_A2") (pintype "output"))
      (node (ref "IC9") (pin "B2") (pinfunction "BULX_B2") (pintype "output"))
      (node (ref "IC9") (pin "C2") (pinfunction "BULX_C2") (pintype "output"))
      (node (ref "L2") (pin "2") (pinfunction "2_2") (pintype "passive"))
    )
    (net (code "54") (name "Net-(IC9-CE)") (class "Default")
      (node (ref "IC9") (pin "D2") (pinfunction "CE_D2") (pintype "input"))
      (node (ref "R1") (pin "1") (pinfunction "1_1") (pintype "passive"))
    )
    (net (code "55") (name "Net-(IC10-REGOUT)") (class "Default")
      (node (ref "C10") (pin "2") (pinfunction "2_2") (pintype "passive"))
      (node (ref "IC10") (pin "10") (pinfunction "REGOUT_10") (pintype "power_in"))
    )
    (net (code "56") (name "Net-(IC11-VIN)") (class "Default")
      (node (ref "C21") (pin "2") (pinfunction "2_2") (pintype "passive"))
      (node (ref "C22") (pin "2") (pinfunction "2_2") (pintype "passive"))
      (node (ref "C24") (pin "2") (pinfunction "2_2") (pintype "passive"))
      (node (ref "IC11") (pin "3") (pinfunction "VIN_3") (pintype "power_in"))
      (node (ref "IC5") (pin "3") (pinfunction "VIN_3") (pintype "power_in"))
      (node (ref "IC6") (pin "3") (pinfunction "VIN_3") (pintype "power_in"))
      (node (ref "SW4") (pin "5") (pinfunction "C2_5") (pintype "passive"))
    )
    (net (code "57") (name "Net-(J1-CC1)") (class "Default")
      (node (ref "J1") (pin "A5") (pinfunction "CC1_A5") (pintype "bidirectional"))
      (node (ref "R30") (pin "2") (pinfunction "2_2") (pintype "passive"))
    )
    (net (code "58") (name "Net-(J1-CC2)") (class "Default")
      (node (ref "J1") (pin "B5") (pinfunction "CC2_B5") (pintype "bidirectional"))
      (node (ref "R31") (pin "2") (pinfunction "2_2") (pintype "passive"))
    )
    (net (code "59") (name "Net-(J2-GND-Pad1)") (class "Default")
      (node (ref "J2") (pin "1") (pinfunction "GND_1") (pintype "bidirectional"))
      (node (ref "J2") (pin "2") (pinfunction "GND_2") (pintype "bidirectional"))
      (node (ref "R37") (pin "2") (pinfunction "2_2") (pintype "passive"))
    )
    (net (code "60") (name "Net-(J6-Pad3)") (class "Default")
      (node (ref "J6") (pin "3") (pinfunction "3_3") (pintype "passive"))
      (node (ref "R8") (pin "1") (pinfunction "1_1") (pintype "passive"))
    )
    (net (code "61") (name "Net-(J6-Pad4)") (class "Default")
      (node (ref "J6") (pin "4") (pinfunction "4_4") (pintype "passive"))
      (node (ref "R16") (pin "1") (pinfunction "1_1") (pintype "passive"))
    )
    (net (code "62") (name "SCK") (class "Default")
      (node (ref "IC1") (pin "32") (pinfunction "IO39_32") (pintype "bidirectional"))
      (node (ref "IC4") (pin "4") (pinfunction "SCK_4") (pintype "input"))
      (node (ref "R28") (pin "1") (pinfunction "1_1") (pintype "passive"))
      (node (ref "SD1") (pin "SCK") (pinfunction "SCK_SCK") (pintype "bidirectional"))
    )
    (net (code "63") (name "SCL") (class "Default")
      (node (ref "IC1") (pin "39") (pinfunction "IO1_39") (pintype "bidirectional"))
      (node (ref "IC8") (pin "7") (pinfunction "SCL_7") (pintype "bidirectional"))
      (node (ref "J4") (pin "4") (pinfunction "4_4") (pintype "passive"))
      (node (ref "R10") (pin "2") (pinfunction "2_2") (pintype "passive"))
      (node (ref "R44") (pin "1") (pinfunction "1_1") (pintype "passive"))
      (node (ref "T8") (pin "6") (pinfunction "D_6") (pintype "passive"))
    )
    (net (code "64") (name "SDA") (class "Default")
      (node (ref "IC1") (pin "38") (pinfunction "IO2_38") (pintype "bidirectional"))
      (node (ref "IC8") (pin "8") (pinfunction "SDA_8") (pintype "bidirectional"))
      (node (ref "J4") (pin "3") (pinfunction "3_3") (pintype "passive"))
      (node (ref "R45") (pin "1") (pinfunction "1_1") (pintype "passive"))
      (node (ref "R9") (pin "2") (pinfunction "2_2") (pintype "passive"))
      (node (ref "T8") (pin "3") (pinfunction "D_3") (pintype "passive"))
    )
    (net (code "65") (name "SDIO_3V3") (class "Default")
      (node (ref "C6") (pin "2") (pinfunction "2_2") (pintype "passive"))
      (node (ref "C7") (pin "2") (pinfunction "2_2") (pintype "passive"))
      (node (ref "Q2") (pin "3") (pinfunction "D_3") (pintype "passive"))
      (node (ref "R26") (pin "2") (pinfunction "2_2") (pintype "passive"))
      (node (ref "R27") (pin "2") (pinfunction "2_2") (pintype "passive"))
      (node (ref "R28") (pin "2") (pinfunction "2_2") (pintype "passive"))
      (node (ref "R29") (pin "2") (pinfunction "2_2") (pintype "passive"))
      (node (ref "SD1") (pin "VCC") (pinfunction "3V3_VCC") (pintype "bidirectional"))
    )
    (net (code "66") (name "SD_ENABLE") (class "Default")
      (node (ref "IC1") (pin "15") (pinfunction "IO3_15") (pintype "bidirectional"))
      (node (ref "Q2") (pin "1") (pinfunction "G_1") (pintype "passive"))
    )
    (net (code "67") (name "SD_SW") (class "Default")
      (node (ref "IC1") (pin "35") (pinfunction "IO42_35") (pintype "bidirectional"))
      (node (ref "R6") (pin "1") (pinfunction "1_1") (pintype "passive"))
      (node (ref "SD1") (pin "SW1") (pinfunction "SW1_SW1") (pintype "bidirectional"))
    )
    (net (code "68") (name "SD_~{CS}") (class "Default")
      (node (ref "IC1") (pin "34") (pinfunction "IO41_34") (pintype "bidirectional"))
      (node (ref "R29") (pin "1") (pinfunction "1_1") (pintype "passive"))
      (node (ref "SD1") (pin "CS") (pinfunction "~{CS}/DAT3_CS") (pintype "bidirectional"))
    )
    (net (code "69") (name "USB-DN") (class "Default")
      (node (ref "D3") (pin "1") (pinfunction "C1_1") (pintype "passive"))
      (node (ref "J1") (pin "A7") (pinfunction "D-_A7") (pintype "bidirectional"))
      (node (ref "J1") (pin "B7") (pinfunction "D-_B7") (pintype "bidirectional"))
      (node (ref "R33") (pin "2") (pinfunction "2_2") (pintype "passive"))
    )
    (net (code "70") (name "USB-DP") (class "Default")
      (node (ref "D3") (pin "2") (pinfunction "C2_2") (pintype "passive"))
      (node (ref "J1") (pin "A6") (pinfunction "D+_A6") (pintype "bidirectional"))
      (node (ref "J1") (pin "B6") (pinfunction "D+_B6") (pintype "bidirectional"))
      (node (ref "R34") (pin "2") (pinfunction "2_2") (pintype "passive"))
    )
    (net (code "71") (name "VBAT") (class "Default")
      (node (ref "C16") (pin "2") (pinfunction "2_2") (pintype "passive"))
      (node (ref "C17") (pin "2") (pinfunction "2_2") (pintype "passive"))
      (node (ref "D2") (pin "6") (pinfunction "VIN2_6") (pintype "power_in"))
      (node (ref "IC3") (pin "3") (pinfunction "VBAT_3") (pintype "bidirectional"))
      (node (ref "IC8") (pin "2") (pinfunction "CELL_2") (pintype "bidirectional"))
      (node (ref "IC8") (pin "3") (pinfunction "VCC_3") (pintype "bidirectional"))
      (node (ref "J3") (pin "1") (pinfunction "1_1") (pintype "passive"))
    )
    (net (code "72") (name "VSWITCHED") (class "Default")
      (node (ref "C25") (pin "2") (pinfunction "2_2") (pintype "passive"))
      (node (ref "C32") (pin "1") (pinfunction "1_1") (pintype "passive"))
      (node (ref "C33") (pin "1") (pinfunction "1_1") (pintype "passive"))
      (node (ref "D2") (pin "2") (pinfunction "VOUT_2") (pintype "power_in"))
      (node (ref "D2") (pin "7") (pinfunction "VOUT_7") (pintype "power_in"))
      (node (ref "IC7") (pin "5") (pinfunction "VIN_5") (pintype "power_in"))
      (node (ref "IC9") (pin "A1") (pinfunction "PVIN_A1") (pintype "power_in"))
      (node (ref "IC9") (pin "B1") (pinfunction "PVIN_B1") (pintype "power_in"))
      (node (ref "IC9") (pin "C1") (pinfunction "PVIN_C1") (pintype "power_in"))
      (node (ref "IC9") (pin "D1") (pinfunction "AVIN_D1") (pintype "power_in"))
      (node (ref "IC9") (pin "D3") (pinfunction "MODE_D3") (pintype "input"))
      (node (ref "SW4") (pin "3") (pinfunction "NC1_3") (pintype "passive"))
      (node (ref "SW4") (pin "6") (pinfunction "NC2_6") (pintype "passive"))
    )
    (net (code "73") (name "VUSB") (class "Default")
      (node (ref "C23") (pin "2") (pinfunction "2_2") (pintype "passive"))
      (node (ref "C28") (pin "2") (pinfunction "2_2") (pintype "passive"))
      (node (ref "D2") (pin "3") (pinfunction "VIN1_3") (pintype "power_in"))
      (node (ref "D4") (pin "A") (pinfunction "A_A") (pintype "passive"))
      (node (ref "IC3") (pin "4") (pinfunction "VIN_4") (pintype "power_in"))
      (node (ref "J1") (pin "VBUS") (pinfunction "VBUS_VBUS") (pintype "power_in"))
      (node (ref "J1") (pin "VBUS2") (pinfunction "VBUS_VBUS2") (pintype "power_in"))
    )
    (net (code "74") (name "V_LED") (class "Default")
      (node (ref "C18") (pin "2") (pinfunction "2_2") (pintype "passive"))
      (node (ref "D1") (pin "4") (pinfunction "VCC_4") (pintype "power_in"))
      (node (ref "R1") (pin "2") (pinfunction "2_2") (pintype "passive"))
      (node (ref "SW4") (pin "2") (pinfunction "C1_2") (pintype "passive"))
    )
    (net (code "75") (name "unconnected-(D1-DO-Pad1)") (class "Default")
      (node (ref "D1") (pin "1") (pinfunction "DO_1") (pintype "bidirectional"))
    )
    (net (code "76") (name "unconnected-(D2-ST-Pad8)") (class "Default")
      (node (ref "D2") (pin "8") (pinfunction "ST_8") (pintype "open_collector"))
    )
    (net (code "77") (name "unconnected-(IC1-IO35-Pad28)") (class "Default")
      (node (ref "IC1") (pin "28") (pinfunction "IO35_28") (pintype "bidirectional"))
    )
    (net (code "78") (name "unconnected-(IC1-IO36-Pad29)") (class "Default")
      (node (ref "IC1") (pin "29") (pinfunction "IO36_29") (pintype "bidirectional"))
    )
    (net (code "79") (name "unconnected-(IC1-IO37-Pad30)") (class "Default")
      (node (ref "IC1") (pin "30") (pinfunction "IO37_30") (pintype "bidirectional"))
    )
    (net (code "80") (name "unconnected-(IC2-NC1-Pad1)") (class "Default")
      (node (ref "IC2") (pin "1") (pinfunction "NC1_1") (pintype "bidirectional"))
    )
    (net (code "81") (name "unconnected-(IC2-Y0-Pad24)") (class "Default")
      (node (ref "IC2") (pin "24") (pinfunction "Y0_24") (pintype "bidirectional"))
    )
    (net (code "82") (name "unconnected-(IC2-Y1-Pad23)") (class "Default")
      (node (ref "IC2") (pin "23") (pinfunction "Y1_23") (pintype "bidirectional"))
    )
    (net (code "83") (name "unconnected-(IC4-DIO2-Pad16)") (class "Default")
      (node (ref "IC4") (pin "16") (pinfunction "DIO2_16") (pintype "bidirectional"))
    )
    (net (code "84") (name "unconnected-(IC4-DIO3-Pad11)") (class "Default")
      (node (ref "IC4") (pin "11") (pinfunction "DIO3_11") (pintype "bidirectional"))
    )
    (net (code "85") (name "unconnected-(IC4-DIO4-Pad12)") (class "Default")
      (node (ref "IC4") (pin "12") (pinfunction "DIO4_12") (pintype "bidirectional"))
    )
    (net (code "86") (name "unconnected-(IC4-DIO5-Pad7)") (class "Default")
      (node (ref "IC4") (pin "7") (pinfunction "DIO5_7") (pintype "bidirectional"))
    )
    (net (code "87") (name "unconnected-(IC8-~{ALERT}-Pad5)") (class "Default")
      (node (ref "IC8") (pin "5") (pinfunction "~{ALERT}_5") (pintype "bidirectional"))
    )
    (net (code "88") (name "unconnected-(IC10-AUX_CL-Pad7)") (class "Default")
      (node (ref "IC10") (pin "7") (pinfunction "AUX_CL_7") (pintype "output"))
    )
    (net (code "89") (name "unconnected-(IC10-AUX_DA-Pad21)") (class "Default")
      (node (ref "IC10") (pin "21") (pinfunction "AUX_DA_21") (pintype "bidirectional"))
    )
    (net (code "90") (name "unconnected-(IC10-INT1-Pad12)") (class "Default")
      (node (ref "IC10") (pin "12") (pinfunction "INT1_12") (pintype "output"))
    )
    (net (code "91") (name "unconnected-(SD1-PadDAT1)") (class "Default")
      (node (ref "SD1") (pin "DAT1") (pinfunction "DAT1_DAT1") (pintype "bidirectional"))
    )
    (net (code "92") (name "unconnected-(SD1-PadDAT2)") (class "Default")
      (node (ref "SD1") (pin "DAT2") (pinfunction "DAT2_DAT2") (pintype "bidirectional"))
    )
    (net (code "93") (name "unconnected-(SW4-NO2-Pad4)") (class "Default")
      (node (ref "SW4") (pin "4") (pinfunction "NO2_4") (pintype "passive"))
    )
  )
)
